# CAN_Connections.net
KiCad netlist of a schematic drawn in Altium Designer
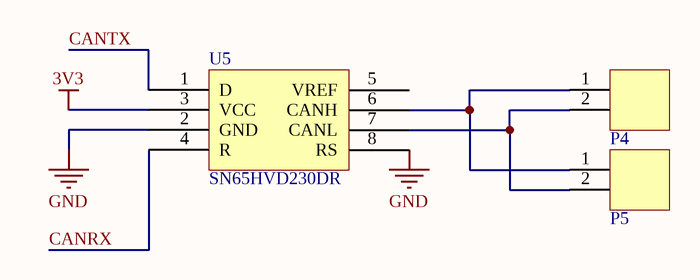
[diagram p0: CAN_Connections.SchDoc]

(export (version "E")
  (design (tool "Eeschema 10.0.6"))
  (components
    (comp (ref "P4")
      (value "2-pin Horz Sherlock")
      (footprint "MOLEX-HDR-1X2-SHERLOCK-HORZ")
      (fields
        (field (name "MANUFACTURER PART NUMBER") "0353630260")
        (field (name "MANUFACTURER") "Molex Inc")
      )
      (libsource (lib "SubjuGator8") (part "MOLEX-HDR-1x2-SHERLOCK_RA"))
    )
    (comp (ref "P5")
      (value "2-pin Horz Sherlock")
      (footprint "MOLEX-HDR-1X2-SHERLOCK-HORZ")
      (fields
        (field (name "MANUFACTURER PART NUMBER") "0353630260")
        (field (name "MANUFACTURER") "Molex Inc")
      )
      (libsource (lib "SubjuGator8") (part "MOLEX-HDR-1x2-SHERLOCK_RA"))
    )
    (comp (ref "U5")
      (value "SN65HVD230DR")
      (footprint "SOIC-8pin")
      (description "IC TXRX CAN 1MBPS 3.3V 8SOIC")
      (libsource (lib "SubjuGator8") (part "SN65HVD230DR"))
    )
  )
  (nets
    (net (code "1") (name "/CANRX") (class "Default")
      (node (ref "U5") (pin "4") (pinfunction "R_4") (pintype "passive"))
    )
    (net (code "2") (name "/CANTX") (class "Default")
      (node (ref "U5") (pin "1") (pinfunction "D_1") (pintype "passive"))
    )
    (net (code "3") (name "3V3") (class "Default")
      (node (ref "U5") (pin "3") (pinfunction "VCC_3") (pintype "passive"))
    )
    (net (code "4") (name "GND") (class "Default")
      (node (ref "U5") (pin "2") (pinfunction "GND_2") (pintype "passive"))
      (node (ref "U5") (pin "8") (pinfunction "RS_8") (pintype "passive"))
    )
    (net (code "5") (name "Net-(U5-CANH)") (class "Default")
      (node (ref "P4") (pin "1") (pinfunction "1_1") (pintype "passive"))
      (node (ref "P5") (pin "1") (pinfunction "1_1") (pintype "passive"))
      (node (ref "U5") (pin "6") (pinfunction "CANH_6") (pintype "passive"))
    )
    (net (code "6") (name "Net-(U5-CANL)") (class "Default")
      (node (ref "P4") (pin "2") (pinfunction "2_2") (pintype "passive"))
      (node (ref "P5") (pin "2") (pinfunction "2_2") (pintype "passive"))
      (node (ref "U5") (pin "7") (pinfunction "CANL_7") (pintype "passive"))
    )
    (net (code "7") (name "unconnected-(U5-VREF-Pad5)") (class "Default")
      (node (ref "U5") (pin "5") (pinfunction "VREF_5") (pintype "passive"))
    )
  )
)
